# CANBridge.net
KiCad netlist of a schematic drawn in EAGLE
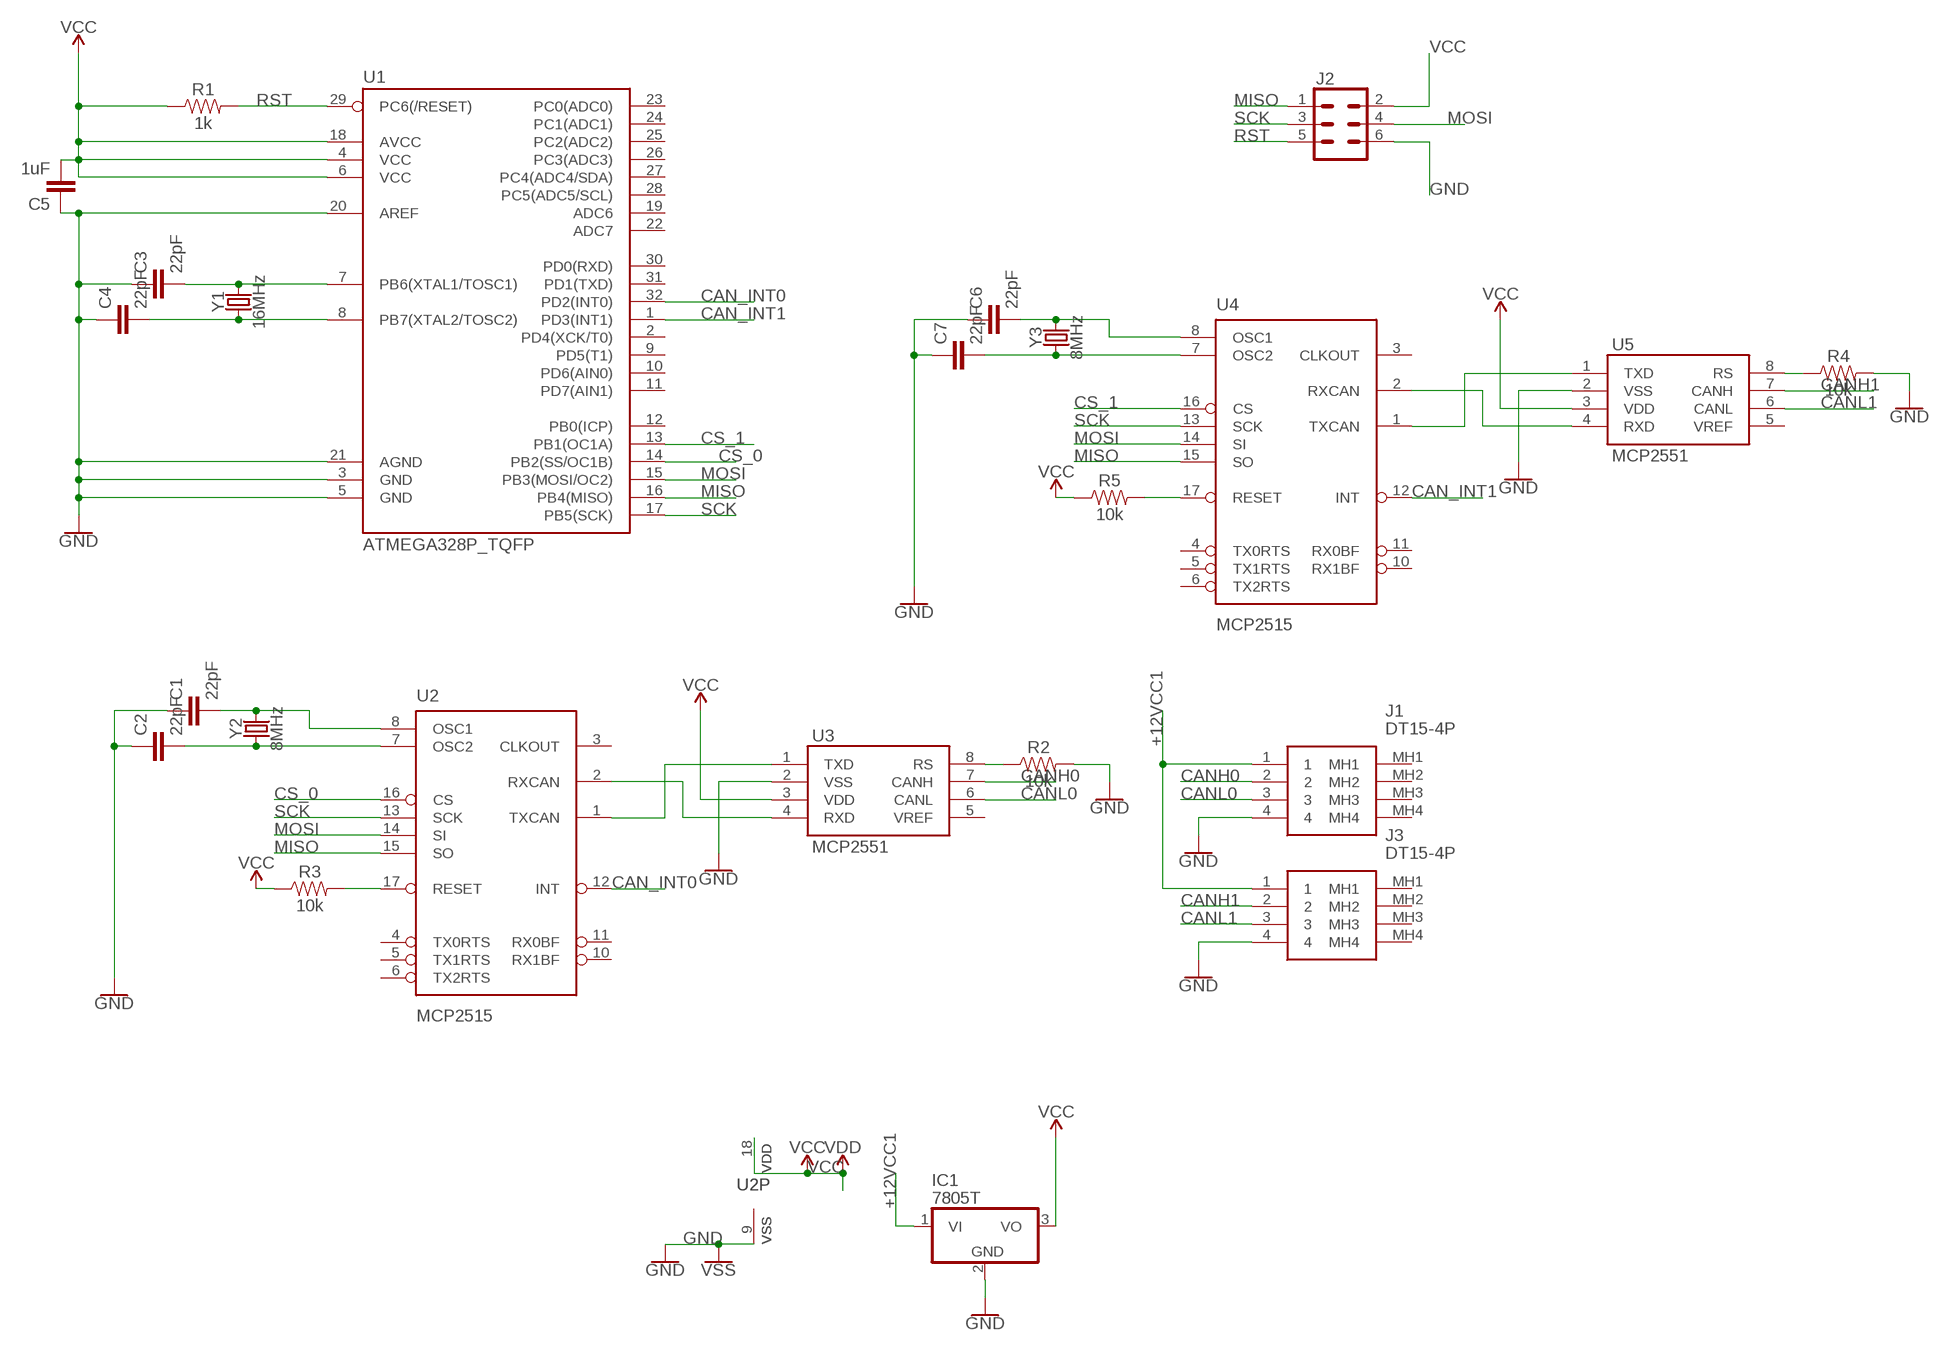
[diagram p0: schematic, sheet 1]

(export (version "E")
  (design (tool "Eeschema 10.0.6"))
  (components
    (comp (ref "C1")
      (value "22pF")
      (footprint "eagle-import:0603")
      (libsource (lib "eagle-import") (part "22PF-0603-50V-5%"))
    )
    (comp (ref "C2")
      (value "22pF")
      (footprint "eagle-import:0603")
      (libsource (lib "eagle-import") (part "22PF-0603-50V-5%"))
    )
    (comp (ref "C3")
      (value "22pF")
      (footprint "eagle-import:0603")
      (libsource (lib "eagle-import") (part "22PF-0603-50V-5%"))
    )
    (comp (ref "C4")
      (value "22pF")
      (footprint "eagle-import:0603")
      (libsource (lib "eagle-import") (part "22PF-0603-50V-5%"))
    )
    (comp (ref "C5")
      (value "1uF")
      (footprint "eagle-import:0603")
      (libsource (lib "eagle-import") (part "22PF-0603-50V-5%"))
    )
    (comp (ref "C6")
      (value "22pF")
      (footprint "eagle-import:0603")
      (libsource (lib "eagle-import") (part "22PF-0603-50V-5%"))
    )
    (comp (ref "C7")
      (value "22pF")
      (footprint "eagle-import:0603")
      (libsource (lib "eagle-import") (part "22PF-0603-50V-5%"))
    )
    (comp (ref "IC1")
      (value "7805T")
      (footprint "eagle-import:TO220H")
      (libsource (lib "eagle-import") (part "78T05"))
    )
    (comp (ref "J1")
      (value "DT15-4P")
      (footprint "eagle-import:DT154P")
      (fields (field (name "MOUSER_PART_NUMBER") "571-DT15-4P"))
      (libsource (lib "eagle-import") (part "DT15-4P"))
    )
    (comp (ref "J2")
      (value "CONN_03X2SHROUD")
      (footprint "eagle-import:2X3-SHROUDED")
      (libsource (lib "eagle-import") (part "CONN_03X2SHROUD"))
    )
    (comp (ref "J3")
      (value "DT15-4P")
      (footprint "eagle-import:DT154P")
      (fields (field (name "MOUSER_PART_NUMBER") "571-DT15-4P"))
      (libsource (lib "eagle-import") (part "DT15-4P"))
    )
    (comp (ref "R1")
      (value "1k")
      (footprint "eagle-import:0603")
      (libsource (lib "eagle-import") (part "1KOHM-0603-1/10W-1%"))
    )
    (comp (ref "R2")
      (value "10k")
      (footprint "eagle-import:0603")
      (libsource (lib "eagle-import") (part "1KOHM-0603-1/10W-1%"))
    )
    (comp (ref "R3")
      (value "10k")
      (footprint "eagle-import:0603")
      (libsource (lib "eagle-import") (part "1KOHM-0603-1/10W-1%"))
    )
    (comp (ref "R4")
      (value "10k")
      (footprint "eagle-import:0603")
      (libsource (lib "eagle-import") (part "1KOHM-0603-1/10W-1%"))
    )
    (comp (ref "R5")
      (value "10k")
      (footprint "eagle-import:0603")
      (libsource (lib "eagle-import") (part "1KOHM-0603-1/10W-1%"))
    )
    (comp (ref "U1")
      (value "ATMEGA328P_TQFP")
      (footprint "eagle-import:TQFP32-08")
      (libsource (lib "eagle-import") (part "ATMEGA328P_TQFP"))
    )
    (comp (ref "U2")
      (value "MCP2515")
      (footprint "eagle-import:SO18W")
      (libsource (lib "eagle-import") (part "MCP2515(MCP2510)SO"))
    )
    (comp (ref "U3")
      (value "MCP2551")
      (footprint "eagle-import:SO08")
      (libsource (lib "eagle-import") (part "MCP2551"))
    )
    (comp (ref "U4")
      (value "MCP2515")
      (footprint "eagle-import:SO18W")
      (libsource (lib "eagle-import") (part "MCP2515(MCP2510)SO"))
    )
    (comp (ref "U5")
      (value "MCP2551")
      (footprint "eagle-import:SO08")
      (libsource (lib "eagle-import") (part "MCP2551"))
    )
    (comp (ref "Y1")
      (value "16MHz")
      (footprint "eagle-import:HC49UP")
      (libsource (lib "eagle-import") (part "CRYSTAL-8MHZSMD-HC49UP"))
    )
    (comp (ref "Y2")
      (value "8MHz")
      (footprint "eagle-import:HC49UP")
      (libsource (lib "eagle-import") (part "CRYSTAL-8MHZSMD-HC49UP"))
    )
    (comp (ref "Y3")
      (value "8MHz")
      (footprint "eagle-import:HC49UP")
      (libsource (lib "eagle-import") (part "CRYSTAL-8MHZSMD-HC49UP"))
    )
  )
  (nets
    (net (code "1") (name "/+12VCC1") (class "Default")
      (node (ref "IC1") (pin "1") (pinfunction "VI_1") (pintype "input"))
      (node (ref "J1") (pin "1") (pinfunction "1_1") (pintype "bidirectional"))
      (node (ref "J3") (pin "1") (pinfunction "1_1") (pintype "bidirectional"))
    )
    (net (code "2") (name "/CANH0") (class "Default")
      (node (ref "J1") (pin "2") (pinfunction "2_2") (pintype "bidirectional"))
      (node (ref "U3") (pin "7") (pinfunction "CANH_7") (pintype "bidirectional"))
    )
    (net (code "3") (name "/CANH1") (class "Default")
      (node (ref "J3") (pin "2") (pinfunction "2_2") (pintype "bidirectional"))
      (node (ref "U5") (pin "7") (pinfunction "CANH_7") (pintype "bidirectional"))
    )
    (net (code "4") (name "/CANL0") (class "Default")
      (node (ref "J1") (pin "3") (pinfunction "3_3") (pintype "bidirectional"))
      (node (ref "U3") (pin "6") (pinfunction "CANL_6") (pintype "bidirectional"))
    )
    (net (code "5") (name "/CANL1") (class "Default")
      (node (ref "J3") (pin "3") (pinfunction "3_3") (pintype "bidirectional"))
      (node (ref "U5") (pin "6") (pinfunction "CANL_6") (pintype "bidirectional"))
    )
    (net (code "6") (name "/CAN_INT0") (class "Default")
      (node (ref "U1") (pin "32") (pinfunction "PD2(INT0)_32") (pintype "bidirectional"))
      (node (ref "U2") (pin "12") (pinfunction "INT_12") (pintype "output"))
    )
    (net (code "7") (name "/CAN_INT1") (class "Default")
      (node (ref "U1") (pin "1") (pinfunction "PD3(INT1)_1") (pintype "bidirectional"))
      (node (ref "U4") (pin "12") (pinfunction "INT_12") (pintype "output"))
    )
    (net (code "8") (name "/CS_0") (class "Default")
      (node (ref "U1") (pin "14") (pinfunction "PB2(SS/OC1B)_14") (pintype "bidirectional"))
      (node (ref "U2") (pin "16") (pinfunction "CS_16") (pintype "input"))
    )
    (net (code "9") (name "/CS_1") (class "Default")
      (node (ref "U1") (pin "13") (pinfunction "PB1(OC1A)_13") (pintype "bidirectional"))
      (node (ref "U4") (pin "16") (pinfunction "CS_16") (pintype "input"))
    )
    (net (code "10") (name "/MISO") (class "Default")
      (node (ref "J2") (pin "1") (pinfunction "1_1") (pintype "bidirectional"))
      (node (ref "U1") (pin "16") (pinfunction "PB4(MISO)_16") (pintype "bidirectional"))
      (node (ref "U2") (pin "15") (pinfunction "SO_15") (pintype "output"))
      (node (ref "U4") (pin "15") (pinfunction "SO_15") (pintype "output"))
    )
    (net (code "11") (name "/MOSI") (class "Default")
      (node (ref "J2") (pin "4") (pinfunction "4_4") (pintype "bidirectional"))
      (node (ref "U1") (pin "15") (pinfunction "PB3(MOSI/OC2)_15") (pintype "bidirectional"))
      (node (ref "U2") (pin "14") (pinfunction "SI_14") (pintype "input"))
      (node (ref "U4") (pin "14") (pinfunction "SI_14") (pintype "input"))
    )
    (net (code "12") (name "/RST") (class "Default")
      (node (ref "J2") (pin "5") (pinfunction "5_5") (pintype "bidirectional"))
      (node (ref "R1") (pin "2") (pinfunction "2_2") (pintype "passive"))
      (node (ref "U1") (pin "29") (pinfunction "PC6(/RESET)_29") (pintype "bidirectional"))
    )
    (net (code "13") (name "/SCK") (class "Default")
      (node (ref "J2") (pin "3") (pinfunction "3_3") (pintype "bidirectional"))
      (node (ref "U1") (pin "17") (pinfunction "PB5(SCK)_17") (pintype "bidirectional"))
      (node (ref "U2") (pin "13") (pinfunction "SCK_13") (pintype "input"))
      (node (ref "U4") (pin "13") (pinfunction "SCK_13") (pintype "input"))
    )
    (net (code "14") (name "GND") (class "Default")
      (node (ref "C1") (pin "1") (pinfunction "1_1") (pintype "passive"))
      (node (ref "C2") (pin "1") (pinfunction "1_1") (pintype "passive"))
      (node (ref "C3") (pin "1") (pinfunction "1_1") (pintype "passive"))
      (node (ref "C4") (pin "1") (pinfunction "1_1") (pintype "passive"))
      (node (ref "C5") (pin "1") (pinfunction "1_1") (pintype "passive"))
      (node (ref "C6") (pin "1") (pinfunction "1_1") (pintype "passive"))
      (node (ref "C7") (pin "1") (pinfunction "1_1") (pintype "passive"))
      (node (ref "IC1") (pin "2") (pinfunction "GND_2") (pintype "passive"))
      (node (ref "J1") (pin "4") (pinfunction "4_4") (pintype "bidirectional"))
      (node (ref "J2") (pin "6") (pinfunction "6_6") (pintype "bidirectional"))
      (node (ref "J3") (pin "4") (pinfunction "4_4") (pintype "bidirectional"))
      (node (ref "R2") (pin "2") (pinfunction "2_2") (pintype "passive"))
      (node (ref "R4") (pin "2") (pinfunction "2_2") (pintype "passive"))
      (node (ref "U1") (pin "20") (pinfunction "AREF_20") (pintype "bidirectional"))
      (node (ref "U1") (pin "21") (pinfunction "AGND_21") (pintype "bidirectional"))
      (node (ref "U1") (pin "3") (pinfunction "GND_3") (pintype "bidirectional"))
      (node (ref "U1") (pin "5") (pinfunction "GND_5") (pintype "bidirectional"))
      (node (ref "U2") (pin "9") (pinfunction "VSS_9") (pintype "power_in"))
      (node (ref "U3") (pin "2") (pinfunction "VSS_2") (pintype "bidirectional"))
      (node (ref "U5") (pin "2") (pinfunction "VSS_2") (pintype "bidirectional"))
    )
    (net (code "15") (name "Net-(U1-PB6(XTAL1{slash}TOSC1))") (class "Default")
      (node (ref "C3") (pin "2") (pinfunction "2_2") (pintype "passive"))
      (node (ref "U1") (pin "7") (pinfunction "PB6(XTAL1/TOSC1)_7") (pintype "bidirectional"))
      (node (ref "Y1") (pin "2") (pinfunction "2_2") (pintype "passive"))
    )
    (net (code "16") (name "Net-(U1-PB7(XTAL2{slash}TOSC2))") (class "Default")
      (node (ref "C4") (pin "2") (pinfunction "2_2") (pintype "passive"))
      (node (ref "U1") (pin "8") (pinfunction "PB7(XTAL2/TOSC2)_8") (pintype "bidirectional"))
      (node (ref "Y1") (pin "1") (pinfunction "1_1") (pintype "passive"))
    )
    (net (code "17") (name "Net-(U2A-OSC1)") (class "Default")
      (node (ref "C1") (pin "2") (pinfunction "2_2") (pintype "passive"))
      (node (ref "U2") (pin "8") (pinfunction "OSC1_8") (pintype "input"))
      (node (ref "Y2") (pin "2") (pinfunction "2_2") (pintype "passive"))
    )
    (net (code "18") (name "Net-(U2A-OSC2)") (class "Default")
      (node (ref "C2") (pin "2") (pinfunction "2_2") (pintype "passive"))
      (node (ref "U2") (pin "7") (pinfunction "OSC2_7") (pintype "output"))
      (node (ref "Y2") (pin "1") (pinfunction "1_1") (pintype "passive"))
    )
    (net (code "19") (name "Net-(U2A-RESET)") (class "Default")
      (node (ref "R3") (pin "2") (pinfunction "2_2") (pintype "passive"))
      (node (ref "U2") (pin "17") (pinfunction "RESET_17") (pintype "input"))
    )
    (net (code "20") (name "Net-(U2A-RXCAN)") (class "Default")
      (node (ref "U2") (pin "2") (pinfunction "RXCAN_2") (pintype "input"))
      (node (ref "U3") (pin "4") (pinfunction "RXD_4") (pintype "bidirectional"))
    )
    (net (code "21") (name "Net-(U2A-TXCAN)") (class "Default")
      (node (ref "U2") (pin "1") (pinfunction "TXCAN_1") (pintype "output"))
      (node (ref "U3") (pin "1") (pinfunction "TXD_1") (pintype "bidirectional"))
    )
    (net (code "22") (name "Net-(U3-RS)") (class "Default")
      (node (ref "R2") (pin "1") (pinfunction "1_1") (pintype "passive"))
      (node (ref "U3") (pin "8") (pinfunction "RS_8") (pintype "bidirectional"))
    )
    (net (code "23") (name "Net-(U4A-OSC1)") (class "Default")
      (node (ref "C6") (pin "2") (pinfunction "2_2") (pintype "passive"))
      (node (ref "U4") (pin "8") (pinfunction "OSC1_8") (pintype "input"))
      (node (ref "Y3") (pin "2") (pinfunction "2_2") (pintype "passive"))
    )
    (net (code "24") (name "Net-(U4A-OSC2)") (class "Default")
      (node (ref "C7") (pin "2") (pinfunction "2_2") (pintype "passive"))
      (node (ref "U4") (pin "7") (pinfunction "OSC2_7") (pintype "output"))
      (node (ref "Y3") (pin "1") (pinfunction "1_1") (pintype "passive"))
    )
    (net (code "25") (name "Net-(U4A-RESET)") (class "Default")
      (node (ref "R5") (pin "2") (pinfunction "2_2") (pintype "passive"))
      (node (ref "U4") (pin "17") (pinfunction "RESET_17") (pintype "input"))
    )
    (net (code "26") (name "Net-(U4A-RXCAN)") (class "Default")
      (node (ref "U4") (pin "2") (pinfunction "RXCAN_2") (pintype "input"))
      (node (ref "U5") (pin "4") (pinfunction "RXD_4") (pintype "bidirectional"))
    )
    (net (code "27") (name "Net-(U4A-TXCAN)") (class "Default")
      (node (ref "U4") (pin "1") (pinfunction "TXCAN_1") (pintype "output"))
      (node (ref "U5") (pin "1") (pinfunction "TXD_1") (pintype "bidirectional"))
    )
    (net (code "28") (name "Net-(U5-RS)") (class "Default")
      (node (ref "R4") (pin "1") (pinfunction "1_1") (pintype "passive"))
      (node (ref "U5") (pin "8") (pinfunction "RS_8") (pintype "bidirectional"))
    )
    (net (code "29") (name "VCC") (class "Default")
      (node (ref "C5") (pin "2") (pinfunction "2_2") (pintype "passive"))
      (node (ref "IC1") (pin "3") (pinfunction "VO_3") (pintype "passive"))
      (node (ref "J2") (pin "2") (pinfunction "2_2") (pintype "bidirectional"))
      (node (ref "R1") (pin "1") (pinfunction "1_1") (pintype "passive"))
      (node (ref "R3") (pin "1") (pinfunction "1_1") (pintype "passive"))
      (node (ref "R5") (pin "1") (pinfunction "1_1") (pintype "passive"))
      (node (ref "U1") (pin "18") (pinfunction "AVCC_18") (pintype "bidirectional"))
      (node (ref "U1") (pin "4") (pinfunction "VCC_4") (pintype "bidirectional"))
      (node (ref "U1") (pin "6") (pinfunction "VCC_6") (pintype "bidirectional"))
      (node (ref "U2") (pin "18") (pinfunction "VDD_18") (pintype "power_in"))
      (node (ref "U3") (pin "3") (pinfunction "VDD_3") (pintype "bidirectional"))
      (node (ref "U5") (pin "3") (pinfunction "VDD_3") (pintype "bidirectional"))
    )
    (net (code "30") (name "unconnected-(J1-PadMH1)") (class "Default")
      (node (ref "J1") (pin "MH1") (pinfunction "MH1_MH1") (pintype "bidirectional"))
    )
    (net (code "31") (name "unconnected-(J1-PadMH2)") (class "Default")
      (node (ref "J1") (pin "MH2") (pinfunction "MH2_MH2") (pintype "bidirectional"))
    )
    (net (code "32") (name "unconnected-(J1-PadMH3)") (class "Default")
      (node (ref "J1") (pin "MH3") (pinfunction "MH3_MH3") (pintype "bidirectional"))
    )
    (net (code "33") (name "unconnected-(J1-PadMH4)") (class "Default")
      (node (ref "J1") (pin "MH4") (pinfunction "MH4_MH4") (pintype "bidirectional"))
    )
    (net (code "34") (name "unconnected-(J3-PadMH1)") (class "Default")
      (node (ref "J3") (pin "MH1") (pinfunction "MH1_MH1") (pintype "bidirectional"))
    )
    (net (code "35") (name "unconnected-(J3-PadMH2)") (class "Default")
      (node (ref "J3") (pin "MH2") (pinfunction "MH2_MH2") (pintype "bidirectional"))
    )
    (net (code "36") (name "unconnected-(J3-PadMH3)") (class "Default")
      (node (ref "J3") (pin "MH3") (pinfunction "MH3_MH3") (pintype "bidirectional"))
    )
    (net (code "37") (name "unconnected-(J3-PadMH4)") (class "Default")
      (node (ref "J3") (pin "MH4") (pinfunction "MH4_MH4") (pintype "bidirectional"))
    )
    (net (code "38") (name "unconnected-(U1-ADC6-Pad19)") (class "Default")
      (node (ref "U1") (pin "19") (pinfunction "ADC6_19") (pintype "bidirectional"))
    )
    (net (code "39") (name "unconnected-(U1-ADC7-Pad22)") (class "Default")
      (node (ref "U1") (pin "22") (pinfunction "ADC7_22") (pintype "bidirectional"))
    )
    (net (code "40") (name "unconnected-(U1-PB0(ICP)-Pad12)") (class "Default")
      (node (ref "U1") (pin "12") (pinfunction "PB0(ICP)_12") (pintype "bidirectional"))
    )
    (net (code "41") (name "unconnected-(U1-PC0(ADC0)-Pad23)") (class "Default")
      (node (ref "U1") (pin "23") (pinfunction "PC0(ADC0)_23") (pintype "bidirectional"))
    )
    (net (code "42") (name "unconnected-(U1-PC1(ADC1)-Pad24)") (class "Default")
      (node (ref "U1") (pin "24") (pinfunction "PC1(ADC1)_24") (pintype "bidirectional"))
    )
    (net (code "43") (name "unconnected-(U1-PC2(ADC2)-Pad25)") (class "Default")
      (node (ref "U1") (pin "25") (pinfunction "PC2(ADC2)_25") (pintype "bidirectional"))
    )
    (net (code "44") (name "unconnected-(U1-PC3(ADC3)-Pad26)") (class "Default")
      (node (ref "U1") (pin "26") (pinfunction "PC3(ADC3)_26") (pintype "bidirectional"))
    )
    (net (code "45") (name "unconnected-(U1-PC4(ADC4{slash}SDA)-Pad27)") (class "Default")
      (node (ref "U1") (pin "27") (pinfunction "PC4(ADC4/SDA)_27") (pintype "bidirectional"))
    )
    (net (code "46") (name "unconnected-(U1-PC5(ADC5{slash}SCL)-Pad28)") (class "Default")
      (node (ref "U1") (pin "28") (pinfunction "PC5(ADC5/SCL)_28") (pintype "bidirectional"))
    )
    (net (code "47") (name "unconnected-(U1-PD0(RXD)-Pad30)") (class "Default")
      (node (ref "U1") (pin "30") (pinfunction "PD0(RXD)_30") (pintype "bidirectional"))
    )
    (net (code "48") (name "unconnected-(U1-PD1(TXD)-Pad31)") (class "Default")
      (node (ref "U1") (pin "31") (pinfunction "PD1(TXD)_31") (pintype "bidirectional"))
    )
    (net (code "49") (name "unconnected-(U1-PD4(XCK{slash}T0)-Pad2)") (class "Default")
      (node (ref "U1") (pin "2") (pinfunction "PD4(XCK/T0)_2") (pintype "bidirectional"))
    )
    (net (code "50") (name "unconnected-(U1-PD5(T1)-Pad9)") (class "Default")
      (node (ref "U1") (pin "9") (pinfunction "PD5(T1)_9") (pintype "bidirectional"))
    )
    (net (code "51") (name "unconnected-(U1-PD6(AIN0)-Pad10)") (class "Default")
      (node (ref "U1") (pin "10") (pinfunction "PD6(AIN0)_10") (pintype "bidirectional"))
    )
    (net (code "52") (name "unconnected-(U1-PD7(AIN1)-Pad11)") (class "Default")
      (node (ref "U1") (pin "11") (pinfunction "PD7(AIN1)_11") (pintype "bidirectional"))
    )
    (net (code "53") (name "unconnected-(U2A-CLKOUT-Pad3)") (class "Default")
      (node (ref "U2") (pin "3") (pinfunction "CLKOUT_3") (pintype "output"))
    )
    (net (code "54") (name "unconnected-(U2A-RX0BF-Pad11)") (class "Default")
      (node (ref "U2") (pin "11") (pinfunction "RX0BF_11") (pintype "output"))
    )
    (net (code "55") (name "unconnected-(U2A-RX1BF-Pad10)") (class "Default")
      (node (ref "U2") (pin "10") (pinfunction "RX1BF_10") (pintype "output"))
    )
    (net (code "56") (name "unconnected-(U2A-TX0RTS-Pad4)") (class "Default")
      (node (ref "U2") (pin "4") (pinfunction "TX0RTS_4") (pintype "input"))
    )
    (net (code "57") (name "unconnected-(U2A-TX1RTS-Pad5)") (class "Default")
      (node (ref "U2") (pin "5") (pinfunction "TX1RTS_5") (pintype "input"))
    )
    (net (code "58") (name "unconnected-(U2A-TX2RTS-Pad6)") (class "Default")
      (node (ref "U2") (pin "6") (pinfunction "TX2RTS_6") (pintype "input"))
    )
    (net (code "59") (name "unconnected-(U3-VREF-Pad5)") (class "Default")
      (node (ref "U3") (pin "5") (pinfunction "VREF_5") (pintype "bidirectional"))
    )
    (net (code "60") (name "unconnected-(U4A-CLKOUT-Pad3)") (class "Default")
      (node (ref "U4") (pin "3") (pinfunction "CLKOUT_3") (pintype "output"))
    )
    (net (code "61") (name "unconnected-(U4A-RX0BF-Pad11)") (class "Default")
      (node (ref "U4") (pin "11") (pinfunction "RX0BF_11") (pintype "output"))
    )
    (net (code "62") (name "unconnected-(U4A-RX1BF-Pad10)") (class "Default")
      (node (ref "U4") (pin "10") (pinfunction "RX1BF_10") (pintype "output"))
    )
    (net (code "63") (name "unconnected-(U4A-TX0RTS-Pad4)") (class "Default")
      (node (ref "U4") (pin "4") (pinfunction "TX0RTS_4") (pintype "input"))
    )
    (net (code "64") (name "unconnected-(U4A-TX1RTS-Pad5)") (class "Default")
      (node (ref "U4") (pin "5") (pinfunction "TX1RTS_5") (pintype "input"))
    )
    (net (code "65") (name "unconnected-(U4A-TX2RTS-Pad6)") (class "Default")
      (node (ref "U4") (pin "6") (pinfunction "TX2RTS_6") (pintype "input"))
    )
    (net (code "66") (name "unconnected-(U5-VREF-Pad5)") (class "Default")
      (node (ref "U5") (pin "5") (pinfunction "VREF_5") (pintype "bidirectional"))
    )
  )
)
